# boost.net
KiCad netlist of a schematic drawn in EAGLE
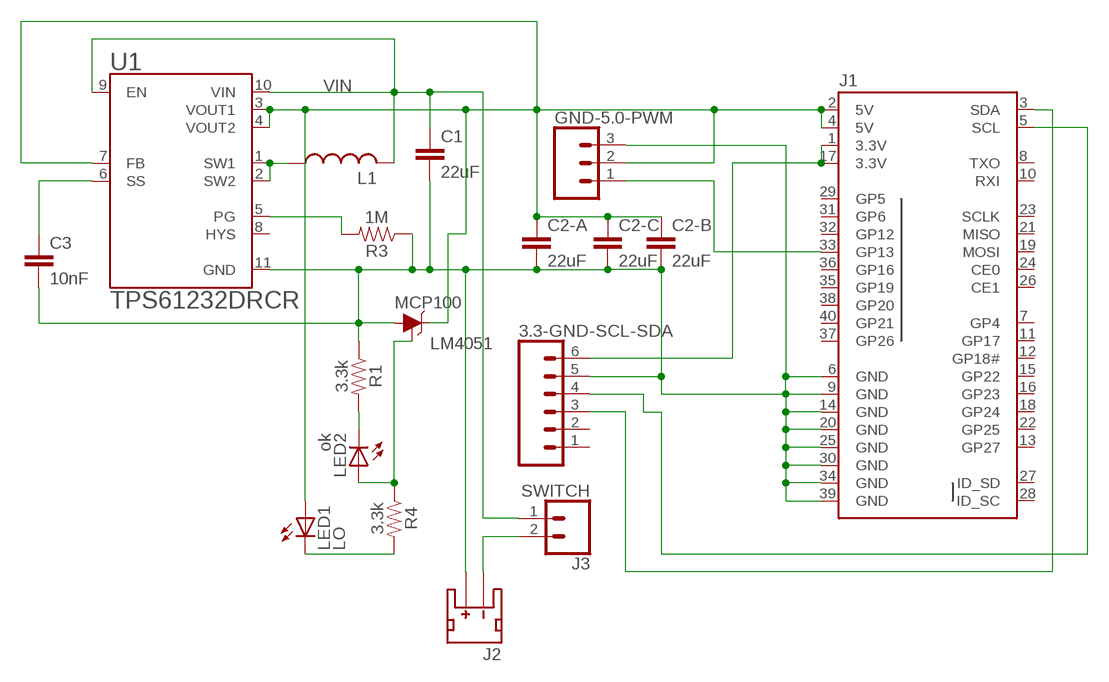
[diagram p0: schematic, sheet 1]

(export (version "E")
  (design (tool "Eeschema 10.0.6"))
  (components
    (comp (ref "3.3-GND-SCL-SDA")
      (value "CONN_06POLAR")
      (footprint "eagle-import:MOLEX-1X6")
      (libsource (lib "eagle-import") (part "CONN_06POLAR"))
    )
    (comp (ref "C1")
      (value "22uF")
      (footprint "eagle-import:C0603")
      (libsource (lib "eagle-import") (part "C-EUC0603"))
    )
    (comp (ref "C2-A")
      (value "22uF")
      (footprint "eagle-import:C0603")
      (libsource (lib "eagle-import") (part "C-EUC0603"))
    )
    (comp (ref "C2-B")
      (value "22uF")
      (footprint "eagle-import:C0603")
      (libsource (lib "eagle-import") (part "C-EUC0603"))
    )
    (comp (ref "C2-C")
      (value "22uF")
      (footprint "eagle-import:C0603")
      (libsource (lib "eagle-import") (part "C-EUC0603"))
    )
    (comp (ref "C3")
      (value "10nF")
      (footprint "eagle-import:C0603")
      (libsource (lib "eagle-import") (part "C-EUC0603"))
    )
    (comp (ref "GND-5.0-PWM")
      (value "CONN_03")
      (footprint "eagle-import:1X03")
      (libsource (lib "eagle-import") (part "CONN_03"))
    )
    (comp (ref "J1")
      (value "RASPBERRYPI-40-PIN-GPIO_PTH_NO_SHROUD")
      (footprint "eagle-import:2X20")
      (libsource (lib "eagle-import") (part "RASPBERRYPI-40-PIN-GPIO_PTH_NO_SHROUD"))
    )
    (comp (ref "J2")
      (value "PWR")
      (footprint "eagle-import:JST-2-SMD")
      (libsource (lib "eagle-import") (part "JST_2MM_MALE"))
    )
    (comp (ref "J3")
      (value "SWITCH")
      (footprint "eagle-import:1X02")
      (libsource (lib "eagle-import") (part "CONN_02"))
    )
    (comp (ref "L1")
      (value "L-USL4532C")
      (footprint "eagle-import:L4532M")
      (libsource (lib "eagle-import") (part "L-USL4532C"))
    )
    (comp (ref "LED1")
      (value "LO")
      (footprint "eagle-import:CHIP-LED0603")
      (libsource (lib "eagle-import") (part "LEDCHIP-LED0603"))
    )
    (comp (ref "LED2")
      (value "ok")
      (footprint "eagle-import:CHIP-LED0603")
      (libsource (lib "eagle-import") (part "LEDCHIP-LED0603"))
    )
    (comp (ref "MCP100")
      (value "LM4051")
      (footprint "eagle-import:SOT23-3")
      (libsource (lib "eagle-import") (part "LM4051"))
    )
    (comp (ref "R1")
      (value "3.3k")
      (footprint "eagle-import:0603")
      (libsource (lib "eagle-import") (part "3.3KOHM-0603-1/10W-1%"))
    )
    (comp (ref "R3")
      (value "1M")
      (footprint "eagle-import:0603")
      (libsource (lib "eagle-import") (part "1.5KOHM-0603-1/10W-1%"))
    )
    (comp (ref "R4")
      (value "3.3k")
      (footprint "eagle-import:0603")
      (libsource (lib "eagle-import") (part "3.3KOHM-0603-1/10W-1%"))
    )
    (comp (ref "U1")
      (value "TPS61232DRCR")
      (footprint "eagle-import:SON50P300X300X100-10N")
      (fields (field (name "DIGI-KEY_PART_NUMBER") "296-44498-1-ND") (field (name "MF") "Texas Instruments"))
      (libsource (lib "eagle-import") (part "TPS61232DRCR"))
    )
  )
  (nets
    (net (code "1") (name "/VIN") (class "Default")
      (node (ref "C1") (pin "1") (pinfunction "1_1") (pintype "passive"))
      (node (ref "J3") (pin "1") (pinfunction "1_1") (pintype "passive"))
      (node (ref "L1") (pin "2") (pinfunction "2_2") (pintype "passive"))
      (node (ref "U1") (pin "10") (pinfunction "VIN_10") (pintype "power_in"))
      (node (ref "U1") (pin "9") (pinfunction "EN_9") (pintype "input"))
    )
    (net (code "2") (name "Net-(3.3-GND-SCL-SDA-Pad6)") (class "Default")
      (node (ref "3.3-GND-SCL-SDA") (pin "6") (pinfunction "6_6") (pintype "passive"))
      (node (ref "J1") (pin "1") (pinfunction "3.3V_1") (pintype "power_in"))
      (node (ref "J1") (pin "17") (pinfunction "3.3V_17") (pintype "power_in"))
    )
    (net (code "3") (name "Net-(J1-GP13)") (class "Default")
      (node (ref "GND-5.0-PWM") (pin "1") (pinfunction "1_1") (pintype "passive"))
      (node (ref "J1") (pin "33") (pinfunction "GP13_33") (pintype "bidirectional"))
    )
    (net (code "4") (name "Net-(J1-SCL)") (class "Default")
      (node (ref "3.3-GND-SCL-SDA") (pin "4") (pinfunction "4_4") (pintype "passive"))
      (node (ref "J1") (pin "5") (pinfunction "SCL_5") (pintype "bidirectional"))
    )
    (net (code "5") (name "Net-(J1-SDA)") (class "Default")
      (node (ref "3.3-GND-SCL-SDA") (pin "3") (pinfunction "3_3") (pintype "passive"))
      (node (ref "J1") (pin "3") (pinfunction "SDA_3") (pintype "bidirectional"))
    )
    (net (code "6") (name "Net-(J2-+)") (class "Default")
      (node (ref "3.3-GND-SCL-SDA") (pin "5") (pinfunction "5_5") (pintype "passive"))
      (node (ref "C1") (pin "2") (pinfunction "2_2") (pintype "passive"))
      (node (ref "C2-A") (pin "2") (pinfunction "2_2") (pintype "passive"))
      (node (ref "C2-B") (pin "2") (pinfunction "2_2") (pintype "passive"))
      (node (ref "C2-C") (pin "2") (pinfunction "2_2") (pintype "passive"))
      (node (ref "C3") (pin "2") (pinfunction "2_2") (pintype "passive"))
      (node (ref "GND-5.0-PWM") (pin "3") (pinfunction "3_3") (pintype "passive"))
      (node (ref "J1") (pin "14") (pinfunction "GND_14") (pintype "power_in"))
      (node (ref "J1") (pin "20") (pinfunction "GND_20") (pintype "power_in"))
      (node (ref "J1") (pin "25") (pinfunction "GND_25") (pintype "power_in"))
      (node (ref "J1") (pin "30") (pinfunction "GND_30") (pintype "power_in"))
      (node (ref "J1") (pin "34") (pinfunction "GND_34") (pintype "power_in"))
      (node (ref "J1") (pin "39") (pinfunction "GND_39") (pintype "power_in"))
      (node (ref "J1") (pin "6") (pinfunction "GND_6") (pintype "power_in"))
      (node (ref "J1") (pin "9") (pinfunction "GND_9") (pintype "power_in"))
      (node (ref "J2") (pin "2") (pinfunction "+_2") (pintype "bidirectional"))
      (node (ref "MCP100") (pin "3") (pinfunction "A_3") (pintype "passive"))
      (node (ref "R1") (pin "1") (pinfunction "1_1") (pintype "passive"))
      (node (ref "R3") (pin "1") (pinfunction "1_1") (pintype "passive"))
      (node (ref "U1") (pin "11") (pinfunction "GND_11") (pintype "power_in"))
    )
    (net (code "7") (name "Net-(J2--)") (class "Default")
      (node (ref "J2") (pin "1") (pinfunction "-_1") (pintype "bidirectional"))
      (node (ref "J3") (pin "2") (pinfunction "2_2") (pintype "passive"))
    )
    (net (code "8") (name "Net-(LED1-PadC)") (class "Default")
      (node (ref "LED1") (pin "C") (pinfunction "C_C") (pintype "passive"))
      (node (ref "R4") (pin "2") (pinfunction "2_2") (pintype "passive"))
    )
    (net (code "9") (name "Net-(LED2-PadC)") (class "Default")
      (node (ref "LED2") (pin "C") (pinfunction "C_C") (pintype "passive"))
      (node (ref "R1") (pin "2") (pinfunction "2_2") (pintype "passive"))
    )
    (net (code "10") (name "Net-(MCP100-ADJ)") (class "Default")
      (node (ref "LED2") (pin "A") (pinfunction "A_A") (pintype "passive"))
      (node (ref "MCP100") (pin "1") (pinfunction "ADJ_1") (pintype "bidirectional"))
      (node (ref "R4") (pin "1") (pinfunction "1_1") (pintype "passive"))
    )
    (net (code "11") (name "Net-(MCP100-C)") (class "Default")
      (node (ref "C2-A") (pin "1") (pinfunction "1_1") (pintype "passive"))
      (node (ref "C2-B") (pin "1") (pinfunction "1_1") (pintype "passive"))
      (node (ref "C2-C") (pin "1") (pinfunction "1_1") (pintype "passive"))
      (node (ref "GND-5.0-PWM") (pin "2") (pinfunction "2_2") (pintype "passive"))
      (node (ref "J1") (pin "2") (pinfunction "5V_2") (pintype "power_in"))
      (node (ref "J1") (pin "4") (pinfunction "5V_4") (pintype "power_in"))
      (node (ref "LED1") (pin "A") (pinfunction "A_A") (pintype "passive"))
      (node (ref "MCP100") (pin "2") (pinfunction "C_2") (pintype "passive"))
      (node (ref "U1") (pin "3") (pinfunction "VOUT1_3") (pintype "power_in"))
      (node (ref "U1") (pin "4") (pinfunction "VOUT2_4") (pintype "power_in"))
      (node (ref "U1") (pin "7") (pinfunction "FB_7") (pintype "input"))
    )
    (net (code "12") (name "Net-(U1-PG)") (class "Default")
      (node (ref "R3") (pin "2") (pinfunction "2_2") (pintype "passive"))
      (node (ref "U1") (pin "5") (pinfunction "PG_5") (pintype "output"))
    )
    (net (code "13") (name "Net-(U1-SS)") (class "Default")
      (node (ref "C3") (pin "1") (pinfunction "1_1") (pintype "passive"))
      (node (ref "U1") (pin "6") (pinfunction "SS_6") (pintype "input"))
    )
    (net (code "14") (name "Net-(U1-SW1)") (class "Default")
      (node (ref "L1") (pin "1") (pinfunction "1_1") (pintype "passive"))
      (node (ref "U1") (pin "1") (pinfunction "SW1_1") (pintype "power_in"))
      (node (ref "U1") (pin "2") (pinfunction "SW2_2") (pintype "power_in"))
    )
    (net (code "15") (name "unconnected-(3.3-GND-SCL-SDA-Pad1)") (class "Default")
      (node (ref "3.3-GND-SCL-SDA") (pin "1") (pinfunction "1_1") (pintype "passive"))
    )
    (net (code "16") (name "unconnected-(3.3-GND-SCL-SDA-Pad2)") (class "Default")
      (node (ref "3.3-GND-SCL-SDA") (pin "2") (pinfunction "2_2") (pintype "passive"))
    )
    (net (code "17") (name "unconnected-(J1-CE0-Pad24)") (class "Default")
      (node (ref "J1") (pin "24") (pinfunction "CE0_24") (pintype "output"))
    )
    (net (code "18") (name "unconnected-(J1-CE1-Pad26)") (class "Default")
      (node (ref "J1") (pin "26") (pinfunction "CE1_26") (pintype "output"))
    )
    (net (code "19") (name "unconnected-(J1-GP4-Pad7)") (class "Default")
      (node (ref "J1") (pin "7") (pinfunction "GP4_7") (pintype "bidirectional"))
    )
    (net (code "20") (name "unconnected-(J1-GP5-Pad29)") (class "Default")
      (node (ref "J1") (pin "29") (pinfunction "GP5_29") (pintype "bidirectional"))
    )
    (net (code "21") (name "unconnected-(J1-GP6-Pad31)") (class "Default")
      (node (ref "J1") (pin "31") (pinfunction "GP6_31") (pintype "bidirectional"))
    )
    (net (code "22") (name "unconnected-(J1-GP12-Pad32)") (class "Default")
      (node (ref "J1") (pin "32") (pinfunction "GP12_32") (pintype "bidirectional"))
    )
    (net (code "23") (name "unconnected-(J1-GP16-Pad36)") (class "Default")
      (node (ref "J1") (pin "36") (pinfunction "GP16_36") (pintype "bidirectional"))
    )
    (net (code "24") (name "unconnected-(J1-GP17-Pad11)") (class "Default")
      (node (ref "J1") (pin "11") (pinfunction "GP17_11") (pintype "bidirectional"))
    )
    (net (code "25") (name "unconnected-(J1-GP18#-Pad12)") (class "Default")
      (node (ref "J1") (pin "12") (pinfunction "GP18#_12") (pintype "bidirectional"))
    )
    (net (code "26") (name "unconnected-(J1-GP19-Pad35)") (class "Default")
      (node (ref "J1") (pin "35") (pinfunction "GP19_35") (pintype "bidirectional"))
    )
    (net (code "27") (name "unconnected-(J1-GP20-Pad38)") (class "Default")
      (node (ref "J1") (pin "38") (pinfunction "GP20_38") (pintype "bidirectional"))
    )
    (net (code "28") (name "unconnected-(J1-GP21-Pad40)") (class "Default")
      (node (ref "J1") (pin "40") (pinfunction "GP21_40") (pintype "bidirectional"))
    )
    (net (code "29") (name "unconnected-(J1-GP22-Pad15)") (class "Default")
      (node (ref "J1") (pin "15") (pinfunction "GP22_15") (pintype "bidirectional"))
    )
    (net (code "30") (name "unconnected-(J1-GP23-Pad16)") (class "Default")
      (node (ref "J1") (pin "16") (pinfunction "GP23_16") (pintype "bidirectional"))
    )
    (net (code "31") (name "unconnected-(J1-GP24-Pad18)") (class "Default")
      (node (ref "J1") (pin "18") (pinfunction "GP24_18") (pintype "bidirectional"))
    )
    (net (code "32") (name "unconnected-(J1-GP25-Pad22)") (class "Default")
      (node (ref "J1") (pin "22") (pinfunction "GP25_22") (pintype "bidirectional"))
    )
    (net (code "33") (name "unconnected-(J1-GP26-Pad37)") (class "Default")
      (node (ref "J1") (pin "37") (pinfunction "GP26_37") (pintype "bidirectional"))
    )
    (net (code "34") (name "unconnected-(J1-GP27-Pad13)") (class "Default")
      (node (ref "J1") (pin "13") (pinfunction "GP27_13") (pintype "bidirectional"))
    )
    (net (code "35") (name "unconnected-(J1-ID_SC-Pad28)") (class "Default")
      (node (ref "J1") (pin "28") (pinfunction "ID_SC_28") (pintype "bidirectional"))
    )
    (net (code "36") (name "unconnected-(J1-ID_SD-Pad27)") (class "Default")
      (node (ref "J1") (pin "27") (pinfunction "ID_SD_27") (pintype "bidirectional"))
    )
    (net (code "37") (name "unconnected-(J1-MISO-Pad21)") (class "Default")
      (node (ref "J1") (pin "21") (pinfunction "MISO_21") (pintype "input"))
    )
    (net (code "38") (name "unconnected-(J1-MOSI-Pad19)") (class "Default")
      (node (ref "J1") (pin "19") (pinfunction "MOSI_19") (pintype "output"))
    )
    (net (code "39") (name "unconnected-(J1-RXI-Pad10)") (class "Default")
      (node (ref "J1") (pin "10") (pinfunction "RXI_10") (pintype "input"))
    )
    (net (code "40") (name "unconnected-(J1-SCLK-Pad23)") (class "Default")
      (node (ref "J1") (pin "23") (pinfunction "SCLK_23") (pintype "output"))
    )
    (net (code "41") (name "unconnected-(J1-TXO-Pad8)") (class "Default")
      (node (ref "J1") (pin "8") (pinfunction "TXO_8") (pintype "output"))
    )
    (net (code "42") (name "unconnected-(J2-PAD1-PadNC1)") (class "Default")
      (node (ref "J2") (pin "NC1") (pinfunction "PAD1_NC1") (pintype "bidirectional"))
    )
    (net (code "43") (name "unconnected-(J2-PAD2-PadNC2)") (class "Default")
      (node (ref "J2") (pin "NC2") (pinfunction "PAD2_NC2") (pintype "bidirectional"))
    )
    (net (code "44") (name "unconnected-(U1-HYS-Pad8)") (class "Default")
      (node (ref "U1") (pin "8") (pinfunction "HYS_8") (pintype "output"))
    )
  )
)
